# OpenArtV3.net
KiCad netlist of a schematic drawn in EasyEDA Pro
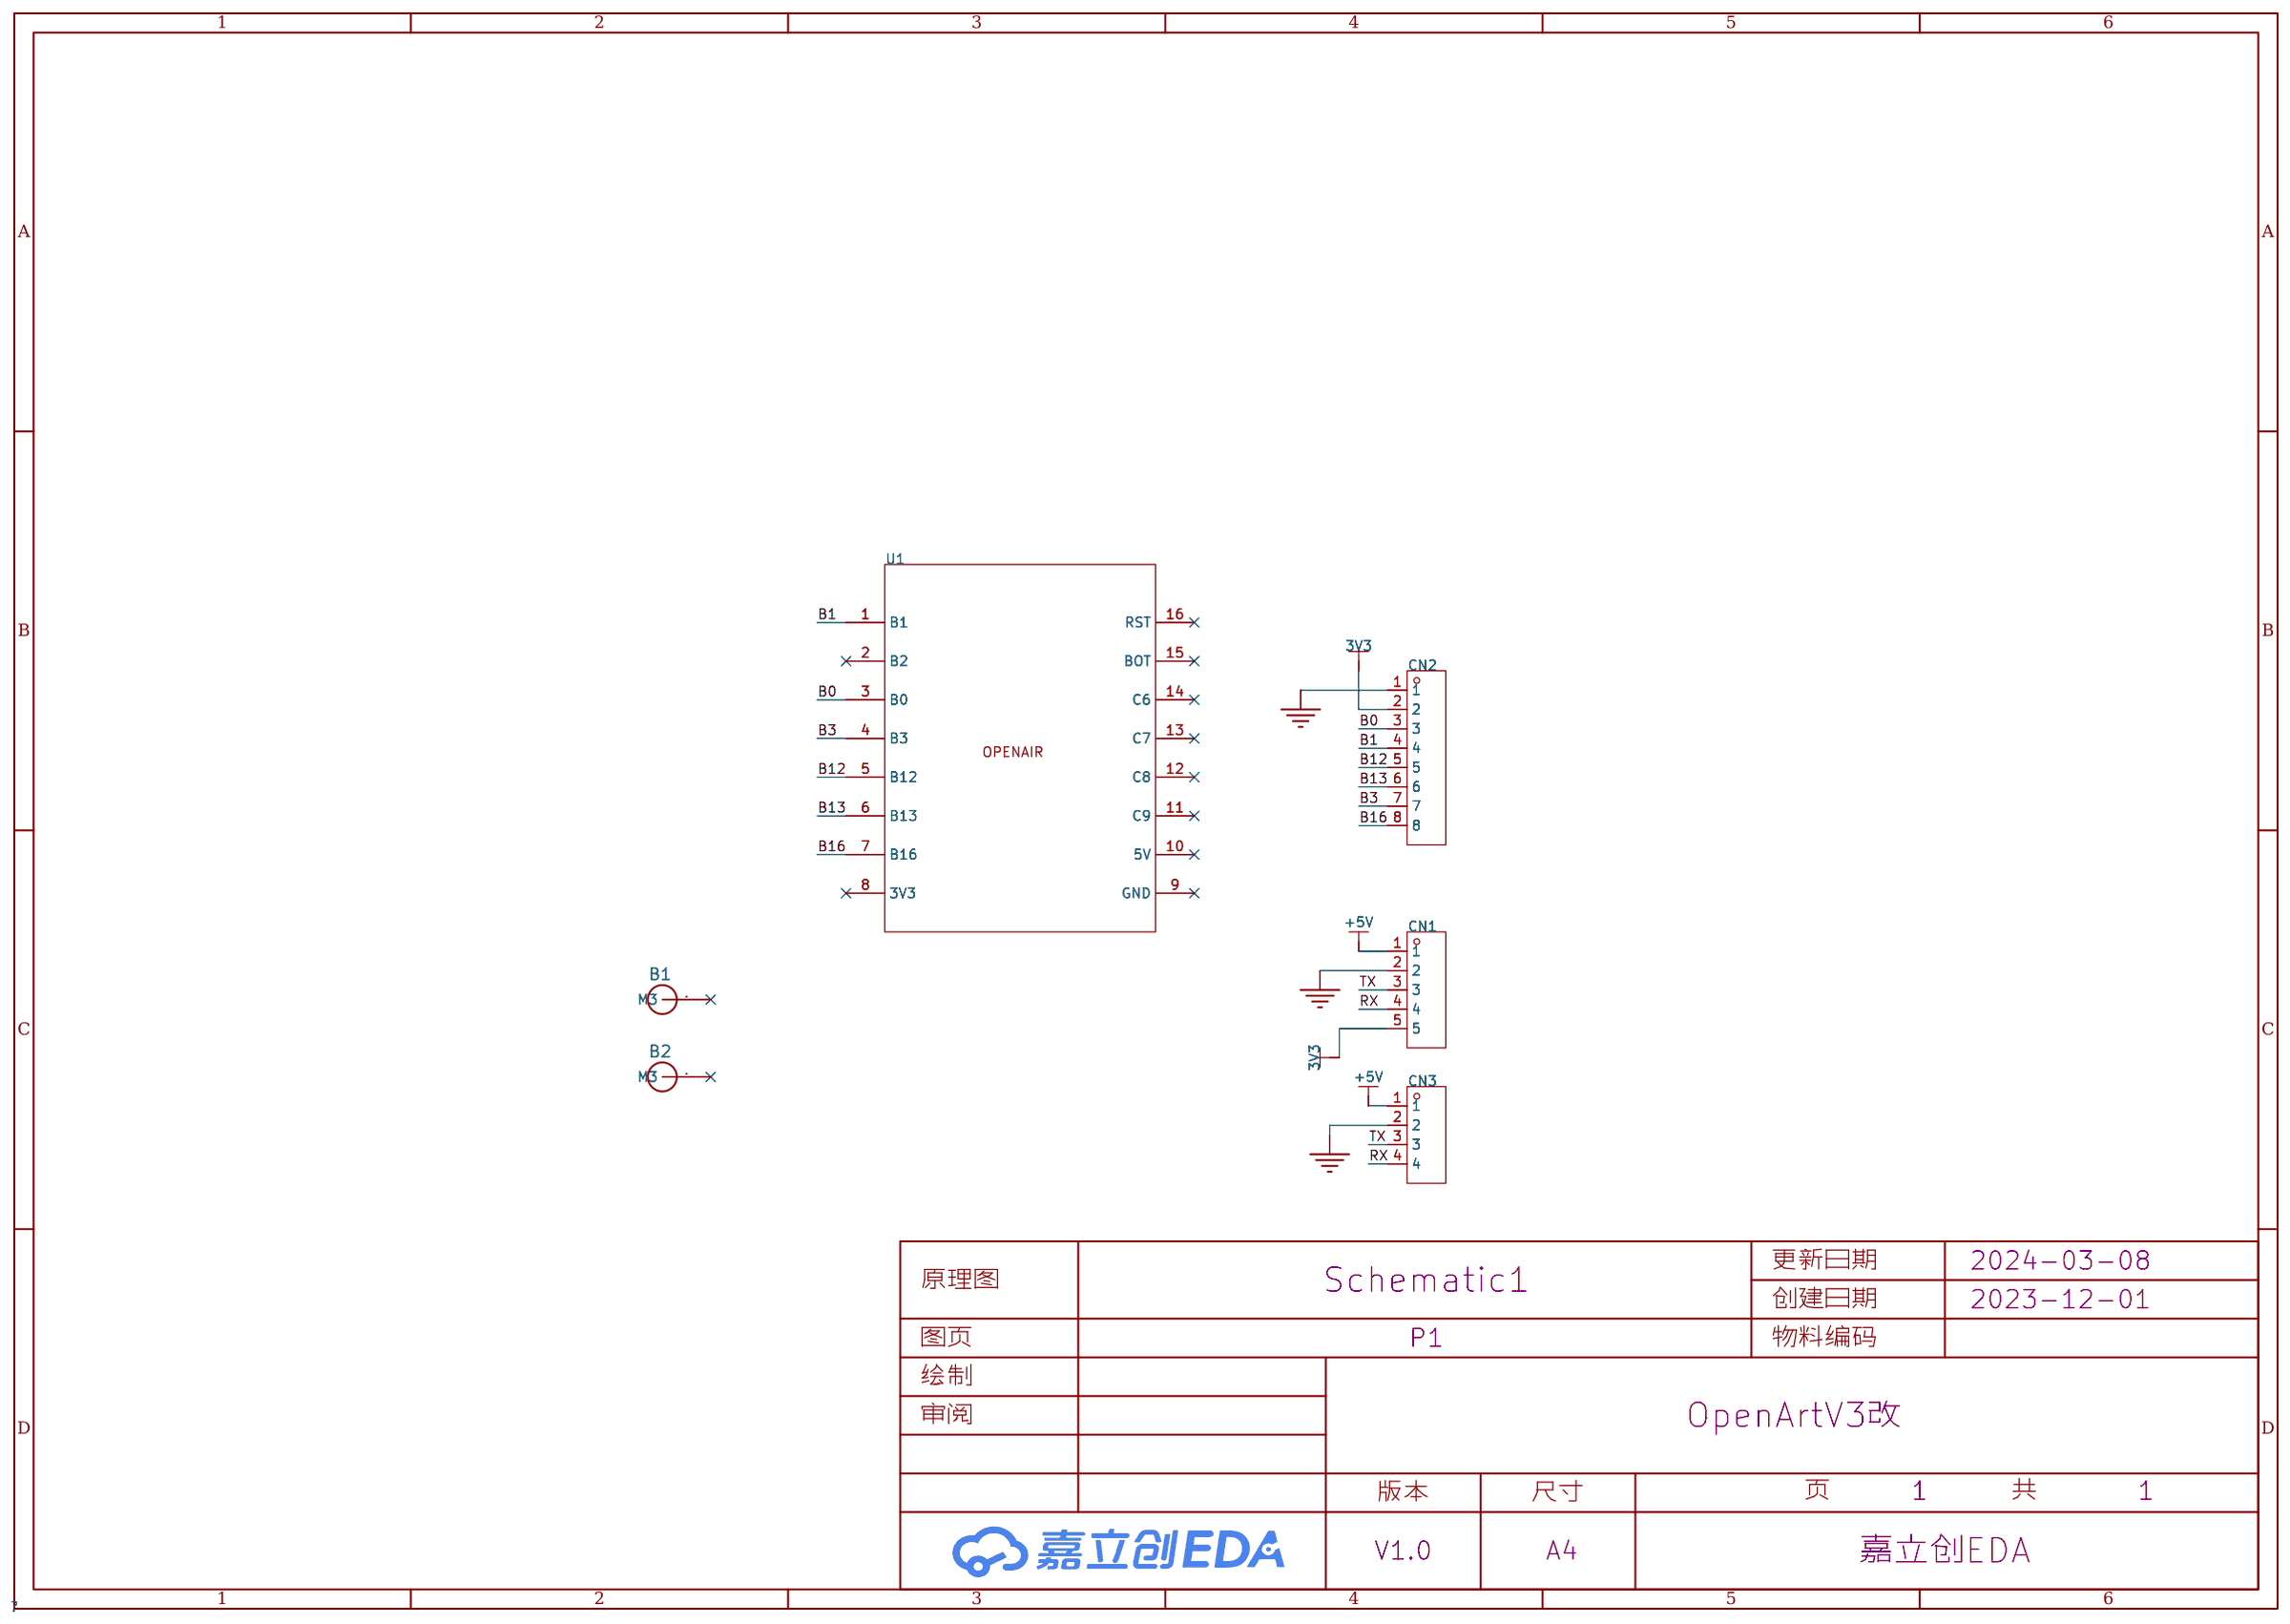
[diagram p0: schematic sheet]

(export (version "E")
  (design (tool "Eeschema 10.0.6"))
  (components
    (comp (ref "B1")
      (value "M3螺柱孔_JX")
      (footprint "easyedapro:M3")
      (libsource (lib "easyedapro") (part "M3螺柱孔_JX"))
    )
    (comp (ref "B2")
      (value "M3螺柱孔_JX")
      (footprint "easyedapro:M3")
      (libsource (lib "easyedapro") (part "M3螺柱孔_JX"))
    )
    (comp (ref "CN1")
      (value "ZX-HA2.54-5PWZ")
      (footprint "easyedapro:CONN-TH_5P-P2.50_ZX-HA2.54-5PWZ")
      (fields (field (name "Manufacturer") "Megastar(兆星)"))
      (libsource (lib "easyedapro") (part "ZX-HA2.54-5PWZ"))
    )
    (comp (ref "CN2")
      (value "BX-XH2.54-8PZZ")
      (footprint "easyedapro:CONN-TH_8P-P2.50_BX-XH2.54-8PZZ")
      (fields (field (name "Manufacturer") "Bossie(博锡)"))
      (libsource (lib "easyedapro") (part "BX-XH2.54-8PZZ"))
    )
    (comp (ref "CN3")
      (value "ZX-XH2.54-4PWZ")
      (footprint "easyedapro:CONN-TH_4P-P2.50_ZX-XH2.54-4PWZ")
      (fields (field (name "Manufacturer") "Megastar(兆星)"))
      (libsource (lib "easyedapro") (part "ZX-XH2.54-4PWZ"))
    )
    (comp (ref "U1") (value "~") (libsource (lib "easyedapro") (part "OPENAIR")))
  )
  (nets
    (net (code "1") (name "+5V") (class "Default")
      (node (ref "CN1") (pin "1") (pinfunction "1_1") (pintype "unspecified"))
      (node (ref "CN3") (pin "1") (pinfunction "1_1") (pintype "unspecified"))
    )
    (net (code "2") (name "/B0") (class "Default")
      (node (ref "CN2") (pin "3") (pinfunction "3_3") (pintype "unspecified"))
      (node (ref "U1") (pin "3") (pinfunction "B0_3") (pintype "input"))
    )
    (net (code "3") (name "/B1") (class "Default")
      (node (ref "CN2") (pin "4") (pinfunction "4_4") (pintype "unspecified"))
      (node (ref "U1") (pin "1") (pinfunction "B1_1") (pintype "input"))
    )
    (net (code "4") (name "/B3") (class "Default")
      (node (ref "CN2") (pin "7") (pinfunction "7_7") (pintype "unspecified"))
      (node (ref "U1") (pin "4") (pinfunction "B3_4") (pintype "input"))
    )
    (net (code "5") (name "/B12") (class "Default")
      (node (ref "CN2") (pin "5") (pinfunction "5_5") (pintype "unspecified"))
      (node (ref "U1") (pin "5") (pinfunction "B12_5") (pintype "input"))
    )
    (net (code "6") (name "/B13") (class "Default")
      (node (ref "CN2") (pin "6") (pinfunction "6_6") (pintype "unspecified"))
      (node (ref "U1") (pin "6") (pinfunction "B13_6") (pintype "input"))
    )
    (net (code "7") (name "/B16") (class "Default")
      (node (ref "CN2") (pin "8") (pinfunction "8_8") (pintype "unspecified"))
      (node (ref "U1") (pin "7") (pinfunction "B16_7") (pintype "input"))
    )
    (net (code "8") (name "/RX") (class "Default")
      (node (ref "CN1") (pin "4") (pinfunction "4_4") (pintype "unspecified"))
      (node (ref "CN3") (pin "4") (pinfunction "4_4") (pintype "unspecified"))
    )
    (net (code "9") (name "/TX") (class "Default")
      (node (ref "CN1") (pin "3") (pinfunction "3_3") (pintype "unspecified"))
      (node (ref "CN3") (pin "3") (pinfunction "3_3") (pintype "unspecified"))
    )
    (net (code "10") (name "3V3") (class "Default")
      (node (ref "CN1") (pin "5") (pinfunction "5_5") (pintype "unspecified"))
      (node (ref "CN2") (pin "2") (pinfunction "2_2") (pintype "unspecified"))
    )
    (net (code "11") (name "GND") (class "Default")
      (node (ref "CN1") (pin "2") (pinfunction "2_2") (pintype "unspecified"))
      (node (ref "CN2") (pin "1") (pinfunction "1_1") (pintype "unspecified"))
      (node (ref "CN3") (pin "2") (pinfunction "2_2") (pintype "unspecified"))
    )
    (net (code "12") (name "unconnected-(B1-M3-Pad1)") (class "Default")
      (node (ref "B1") (pin "1") (pinfunction "M3_1") (pintype "input+no_connect"))
    )
    (net (code "13") (name "unconnected-(B2-M3-Pad1)") (class "Default")
      (node (ref "B2") (pin "1") (pinfunction "M3_1") (pintype "input+no_connect"))
    )
    (net (code "14") (name "unconnected-(U1-3V3-Pad8)") (class "Default")
      (node (ref "U1") (pin "8") (pinfunction "3V3_8") (pintype "input+no_connect"))
    )
    (net (code "15") (name "unconnected-(U1-5V-Pad10)") (class "Default")
      (node (ref "U1") (pin "10") (pinfunction "5V_10") (pintype "input+no_connect"))
    )
    (net (code "16") (name "unconnected-(U1-B2-Pad2)") (class "Default")
      (node (ref "U1") (pin "2") (pinfunction "B2_2") (pintype "input+no_connect"))
    )
    (net (code "17") (name "unconnected-(U1-BOT-Pad15)") (class "Default")
      (node (ref "U1") (pin "15") (pinfunction "BOT_15") (pintype "input+no_connect"))
    )
    (net (code "18") (name "unconnected-(U1-C6-Pad14)") (class "Default")
      (node (ref "U1") (pin "14") (pinfunction "C6_14") (pintype "input+no_connect"))
    )
    (net (code "19") (name "unconnected-(U1-C7-Pad13)") (class "Default")
      (node (ref "U1") (pin "13") (pinfunction "C7_13") (pintype "input+no_connect"))
    )
    (net (code "20") (name "unconnected-(U1-C8-Pad12)") (class "Default")
      (node (ref "U1") (pin "12") (pinfunction "C8_12") (pintype "input+no_connect"))
    )
    (net (code "21") (name "unconnected-(U1-C9-Pad11)") (class "Default")
      (node (ref "U1") (pin "11") (pinfunction "C9_11") (pintype "input+no_connect"))
    )
    (net (code "22") (name "unconnected-(U1-GND-Pad9)") (class "Default")
      (node (ref "U1") (pin "9") (pinfunction "GND_9") (pintype "input+no_connect"))
    )
    (net (code "23") (name "unconnected-(U1-RST-Pad16)") (class "Default")
      (node (ref "U1") (pin "16") (pinfunction "RST_16") (pintype "input+no_connect"))
    )
  )
)
